# hub-i-proto-pcbant01.net
KiCad netlist of a schematic drawn in EAGLE
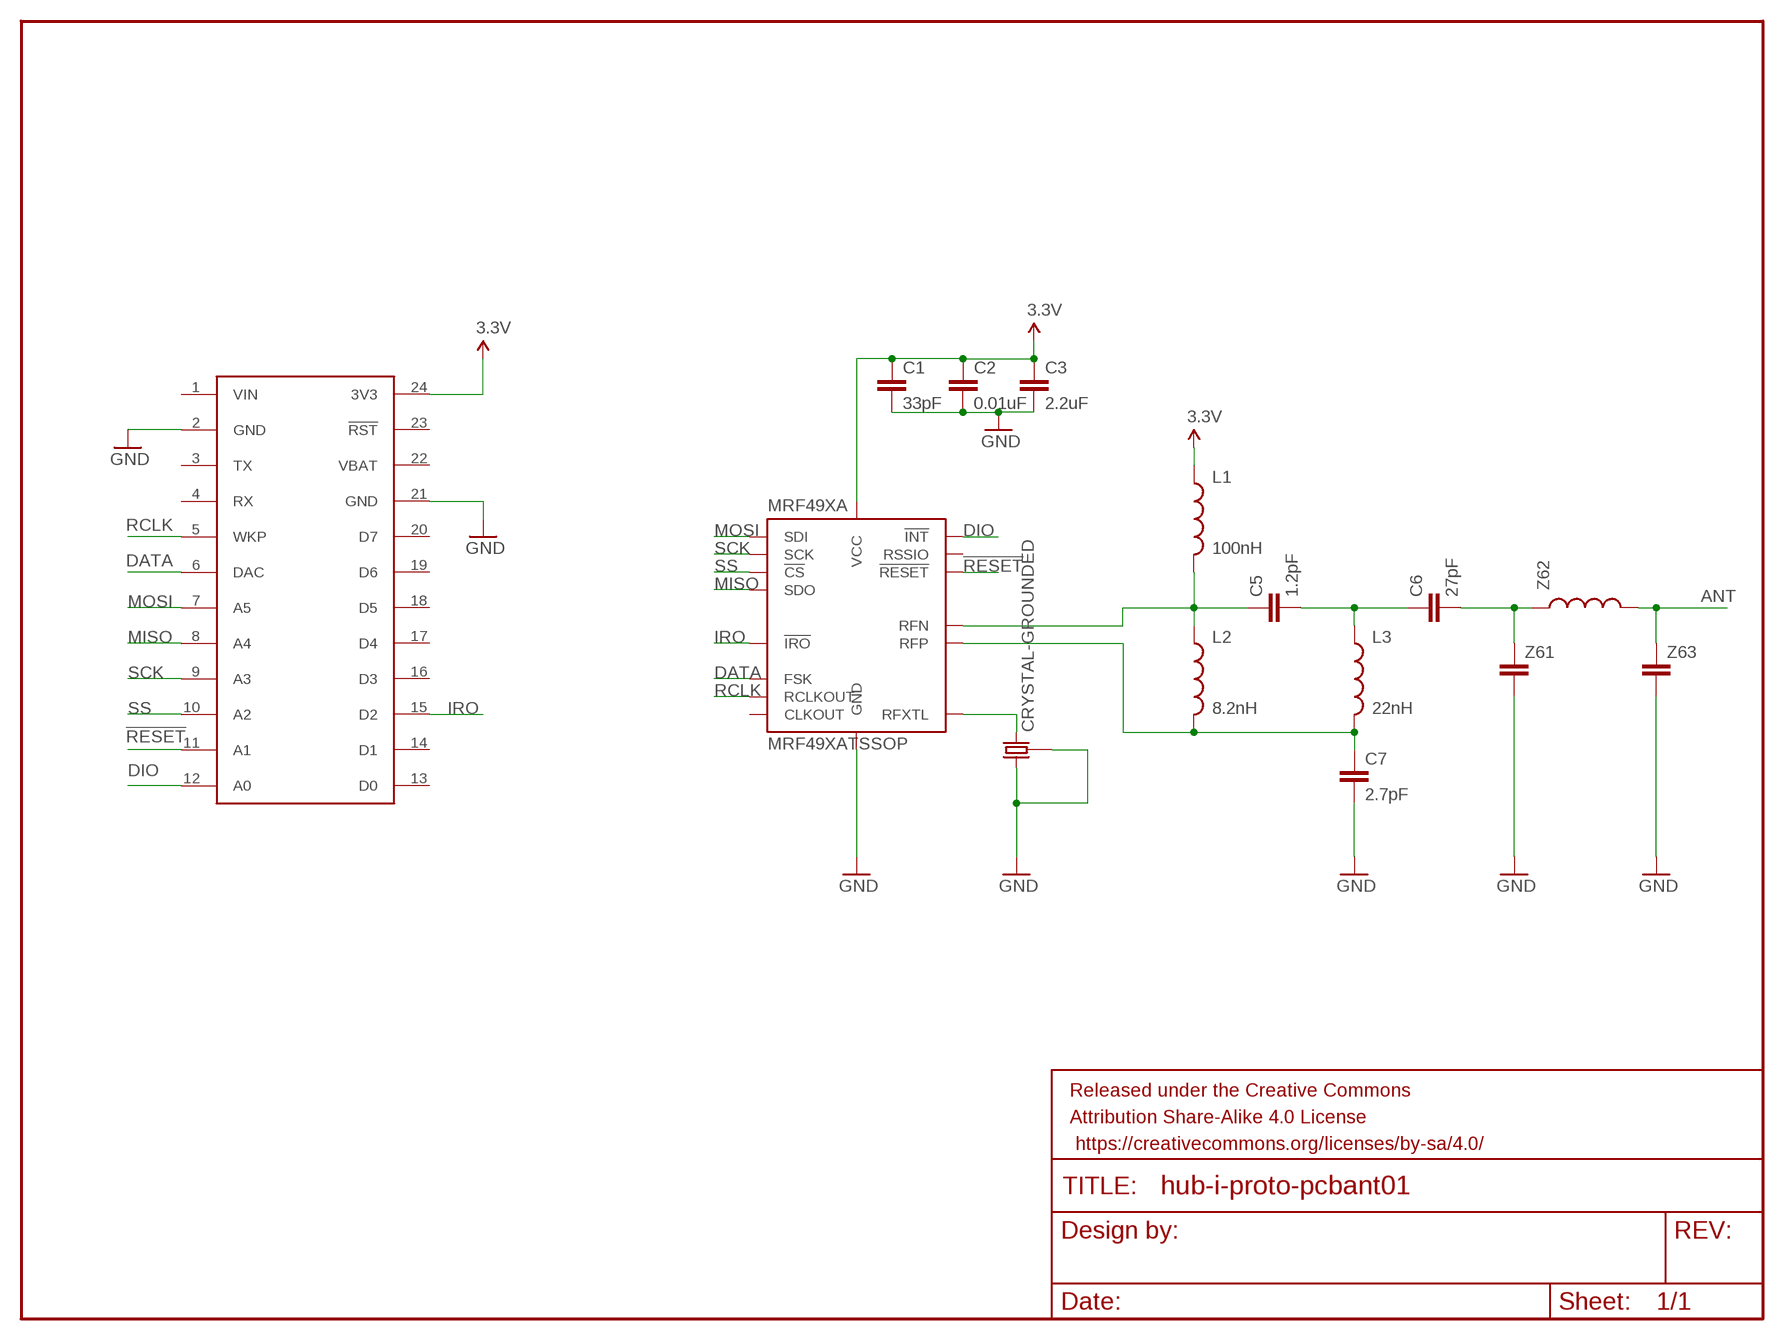
[diagram p0: schematic, sheet 1]

(export (version "E")
  (design (tool "Eeschema 10.0.6"))
  (components
    (comp (ref "C1")
      (value "33pF")
      (footprint "eagle-import:0603-CAP")
      (libsource (lib "eagle-import") (part "CAP0603-CAP"))
    )
    (comp (ref "C2")
      (value "0.01uF")
      (footprint "eagle-import:0603-CAP")
      (libsource (lib "eagle-import") (part "CAP0603-CAP"))
    )
    (comp (ref "C3")
      (value "2.2uF")
      (footprint "eagle-import:0603-CAP")
      (libsource (lib "eagle-import") (part "CAP0603-CAP"))
    )
    (comp (ref "C5")
      (value "1.2pF")
      (footprint "eagle-import:0603-CAP")
      (libsource (lib "eagle-import") (part "CAP0603-CAP"))
    )
    (comp (ref "C6")
      (value "27pF")
      (footprint "eagle-import:0603-CAP")
      (libsource (lib "eagle-import") (part "CAP0603-CAP"))
    )
    (comp (ref "C7")
      (value "2.7pF")
      (footprint "eagle-import:0603-CAP")
      (libsource (lib "eagle-import") (part "CAP0603-CAP"))
    )
    (comp (ref "CORE")
      (value "SPARK_CORECORE")
      (footprint "eagle-import:SPARK_CORE")
      (libsource (lib "eagle-import") (part "SPARK_CORECORE"))
    )
    (comp (ref "FRAME1")
      (value "FRAME-LETTER")
      (footprint "eagle-import:CREATIVE_COMMONS")
      (libsource (lib "eagle-import") (part "FRAME-LETTER"))
    )
    (comp (ref "L1")
      (value "100nH")
      (footprint "eagle-import:0603")
      (libsource (lib "eagle-import") (part "INDUCTOR0603"))
    )
    (comp (ref "L2")
      (value "8.2nH")
      (footprint "eagle-import:0603")
      (libsource (lib "eagle-import") (part "INDUCTOR0603"))
    )
    (comp (ref "L3")
      (value "22nH")
      (footprint "eagle-import:0603")
      (libsource (lib "eagle-import") (part "INDUCTOR0603"))
    )
    (comp (ref "MRF49XA")
      (value "MRF49XATSSOP")
      (footprint "eagle-import:TSSOP16")
      (libsource (lib "eagle-import") (part "MRF49XATSSOP"))
    )
    (comp (ref "Y1")
      (value "CRYSTAL-GROUNDED")
      (footprint "eagle-import:CRYSTAL-SMD-5X3")
      (libsource (lib "eagle-import") (part "CRYSTAL-GROUNDED"))
    )
    (comp (ref "Z61")
      (value "CAP0603-CAP")
      (footprint "eagle-import:0603-CAP")
      (libsource (lib "eagle-import") (part "CAP0603-CAP"))
    )
    (comp (ref "Z62")
      (value "INDUCTOR0603")
      (footprint "eagle-import:0603")
      (libsource (lib "eagle-import") (part "INDUCTOR0603"))
    )
    (comp (ref "Z63")
      (value "CAP0603-CAP")
      (footprint "eagle-import:0603-CAP")
      (libsource (lib "eagle-import") (part "CAP0603-CAP"))
    )
  )
  (nets
    (net (code "1") (name "/ANT") (class "Default")
      (node (ref "Z62") (pin "2") (pinfunction "2_2") (pintype "passive"))
      (node (ref "Z63") (pin "1") (pinfunction "1_1") (pintype "passive"))
    )
    (net (code "2") (name "/DATA") (class "Default")
      (node (ref "CORE") (pin "6") (pinfunction "DAC_6") (pintype "bidirectional"))
      (node (ref "MRF49XA") (pin "6") (pinfunction "FSK_6") (pintype "bidirectional"))
    )
    (net (code "3") (name "/DIO") (class "Default")
      (node (ref "CORE") (pin "12") (pinfunction "A0_12") (pintype "bidirectional"))
      (node (ref "MRF49XA") (pin "16") (pinfunction "~{INT}_16") (pintype "bidirectional"))
    )
    (net (code "4") (name "/IRO") (class "Default")
      (node (ref "CORE") (pin "15") (pinfunction "D2_15") (pintype "bidirectional"))
      (node (ref "MRF49XA") (pin "5") (pinfunction "~{IRO}_5") (pintype "output"))
    )
    (net (code "5") (name "/MISO") (class "Default")
      (node (ref "CORE") (pin "8") (pinfunction "A4_8") (pintype "bidirectional"))
      (node (ref "MRF49XA") (pin "4") (pinfunction "SDO_4") (pintype "output"))
    )
    (net (code "6") (name "/MOSI") (class "Default")
      (node (ref "CORE") (pin "7") (pinfunction "A5_7") (pintype "bidirectional"))
      (node (ref "MRF49XA") (pin "1") (pinfunction "SDI_1") (pintype "input"))
    )
    (net (code "7") (name "/RCLK") (class "Default")
      (node (ref "CORE") (pin "5") (pinfunction "WKP_5") (pintype "bidirectional"))
      (node (ref "MRF49XA") (pin "7") (pinfunction "RCLKOUT_7") (pintype "bidirectional"))
    )
    (net (code "8") (name "/SCK") (class "Default")
      (node (ref "CORE") (pin "9") (pinfunction "A3_9") (pintype "bidirectional"))
      (node (ref "MRF49XA") (pin "2") (pinfunction "SCK_2") (pintype "input"))
    )
    (net (code "9") (name "/SS") (class "Default")
      (node (ref "CORE") (pin "10") (pinfunction "A2_10") (pintype "bidirectional"))
      (node (ref "MRF49XA") (pin "3") (pinfunction "~{CS}_3") (pintype "input"))
    )
    (net (code "10") (name "/VBAT") (class "Default")
      (node (ref "CORE") (pin "22") (pinfunction "VBAT_22") (pintype "power_in"))
    )
    (net (code "11") (name "/VIN") (class "Default")
      (node (ref "CORE") (pin "1") (pinfunction "VIN_1") (pintype "power_in"))
    )
    (net (code "12") (name "/~{RESET}") (class "Default")
      (node (ref "CORE") (pin "11") (pinfunction "A1_11") (pintype "bidirectional"))
      (node (ref "MRF49XA") (pin "10") (pinfunction "~{RESET}_10") (pintype "bidirectional"))
    )
    (net (code "13") (name "3.3V") (class "Default")
      (node (ref "C1") (pin "1") (pinfunction "1_1") (pintype "passive"))
      (node (ref "C2") (pin "1") (pinfunction "1_1") (pintype "passive"))
      (node (ref "C3") (pin "1") (pinfunction "1_1") (pintype "passive"))
      (node (ref "CORE") (pin "24") (pinfunction "3V3_24") (pintype "power_in"))
      (node (ref "L1") (pin "1") (pinfunction "1_1") (pintype "passive"))
      (node (ref "MRF49XA") (pin "14") (pinfunction "VCC_14") (pintype "power_in"))
    )
    (net (code "14") (name "GND") (class "Default")
      (node (ref "C1") (pin "2") (pinfunction "2_2") (pintype "passive"))
      (node (ref "C2") (pin "2") (pinfunction "2_2") (pintype "passive"))
      (node (ref "C3") (pin "2") (pinfunction "2_2") (pintype "passive"))
      (node (ref "C7") (pin "2") (pinfunction "2_2") (pintype "passive"))
      (node (ref "CORE") (pin "2") (pinfunction "GND_2") (pintype "power_in"))
      (node (ref "CORE") (pin "21") (pinfunction "GND_21") (pintype "power_in"))
      (node (ref "MRF49XA") (pin "11") (pinfunction "GND_11") (pintype "power_in"))
      (node (ref "Y1") (pin "2") (pinfunction "3_2") (pintype "passive"))
      (node (ref "Y1") (pin "3") (pinfunction "1_3") (pintype "passive"))
      (node (ref "Y1") (pin "4") (pinfunction "3_4") (pintype "passive"))
      (node (ref "Z61") (pin "2") (pinfunction "2_2") (pintype "passive"))
      (node (ref "Z63") (pin "2") (pinfunction "2_2") (pintype "passive"))
    )
    (net (code "15") (name "Net-(C5-Pad2)") (class "Default")
      (node (ref "C5") (pin "2") (pinfunction "2_2") (pintype "passive"))
      (node (ref "C6") (pin "1") (pinfunction "1_1") (pintype "passive"))
      (node (ref "L3") (pin "1") (pinfunction "1_1") (pintype "passive"))
    )
    (net (code "16") (name "Net-(C6-Pad2)") (class "Default")
      (node (ref "C6") (pin "2") (pinfunction "2_2") (pintype "passive"))
      (node (ref "Z61") (pin "1") (pinfunction "1_1") (pintype "passive"))
      (node (ref "Z62") (pin "1") (pinfunction "1_1") (pintype "passive"))
    )
    (net (code "17") (name "Net-(MRF49XA-RFN)") (class "Default")
      (node (ref "C5") (pin "1") (pinfunction "1_1") (pintype "passive"))
      (node (ref "L1") (pin "2") (pinfunction "2_2") (pintype "passive"))
      (node (ref "L2") (pin "1") (pinfunction "1_1") (pintype "passive"))
      (node (ref "MRF49XA") (pin "13") (pinfunction "RFN_13") (pintype "bidirectional"))
    )
    (net (code "18") (name "Net-(MRF49XA-RFP)") (class "Default")
      (node (ref "C7") (pin "1") (pinfunction "1_1") (pintype "passive"))
      (node (ref "L2") (pin "2") (pinfunction "2_2") (pintype "passive"))
      (node (ref "L3") (pin "2") (pinfunction "2_2") (pintype "passive"))
      (node (ref "MRF49XA") (pin "12") (pinfunction "RFP_12") (pintype "bidirectional"))
    )
    (net (code "19") (name "Net-(MRF49XA-RFXTL)") (class "Default")
      (node (ref "MRF49XA") (pin "9") (pinfunction "RFXTL_9") (pintype "input"))
      (node (ref "Y1") (pin "1") (pinfunction "2_1") (pintype "passive"))
    )
    (net (code "20") (name "unconnected-(CORE-D0-Pad13)") (class "Default")
      (node (ref "CORE") (pin "13") (pinfunction "D0_13") (pintype "bidirectional"))
    )
    (net (code "21") (name "unconnected-(CORE-D1-Pad14)") (class "Default")
      (node (ref "CORE") (pin "14") (pinfunction "D1_14") (pintype "bidirectional"))
    )
    (net (code "22") (name "unconnected-(CORE-D3-Pad16)") (class "Default")
      (node (ref "CORE") (pin "16") (pinfunction "D3_16") (pintype "bidirectional"))
    )
    (net (code "23") (name "unconnected-(CORE-D4-Pad17)") (class "Default")
      (node (ref "CORE") (pin "17") (pinfunction "D4_17") (pintype "bidirectional"))
    )
    (net (code "24") (name "unconnected-(CORE-D5-Pad18)") (class "Default")
      (node (ref "CORE") (pin "18") (pinfunction "D5_18") (pintype "bidirectional"))
    )
    (net (code "25") (name "unconnected-(CORE-D6-Pad19)") (class "Default")
      (node (ref "CORE") (pin "19") (pinfunction "D6_19") (pintype "bidirectional"))
    )
    (net (code "26") (name "unconnected-(CORE-D7-Pad20)") (class "Default")
      (node (ref "CORE") (pin "20") (pinfunction "D7_20") (pintype "bidirectional"))
    )
    (net (code "27") (name "unconnected-(CORE-RX-Pad4)") (class "Default")
      (node (ref "CORE") (pin "4") (pinfunction "RX_4") (pintype "bidirectional"))
    )
    (net (code "28") (name "unconnected-(CORE-TX-Pad3)") (class "Default")
      (node (ref "CORE") (pin "3") (pinfunction "TX_3") (pintype "bidirectional"))
    )
    (net (code "29") (name "unconnected-(CORE-~{RST}-Pad23)") (class "Default")
      (node (ref "CORE") (pin "23") (pinfunction "~{RST}_23") (pintype "bidirectional"))
    )
    (net (code "30") (name "unconnected-(MRF49XA-CLKOUT-Pad8)") (class "Default")
      (node (ref "MRF49XA") (pin "8") (pinfunction "CLKOUT_8") (pintype "output"))
    )
    (net (code "31") (name "unconnected-(MRF49XA-RSSIO-Pad15)") (class "Default")
      (node (ref "MRF49XA") (pin "15") (pinfunction "RSSIO_15") (pintype "bidirectional"))
    )
  )
)
